# M105X.net
KiCad netlist of a schematic drawn in EAGLE
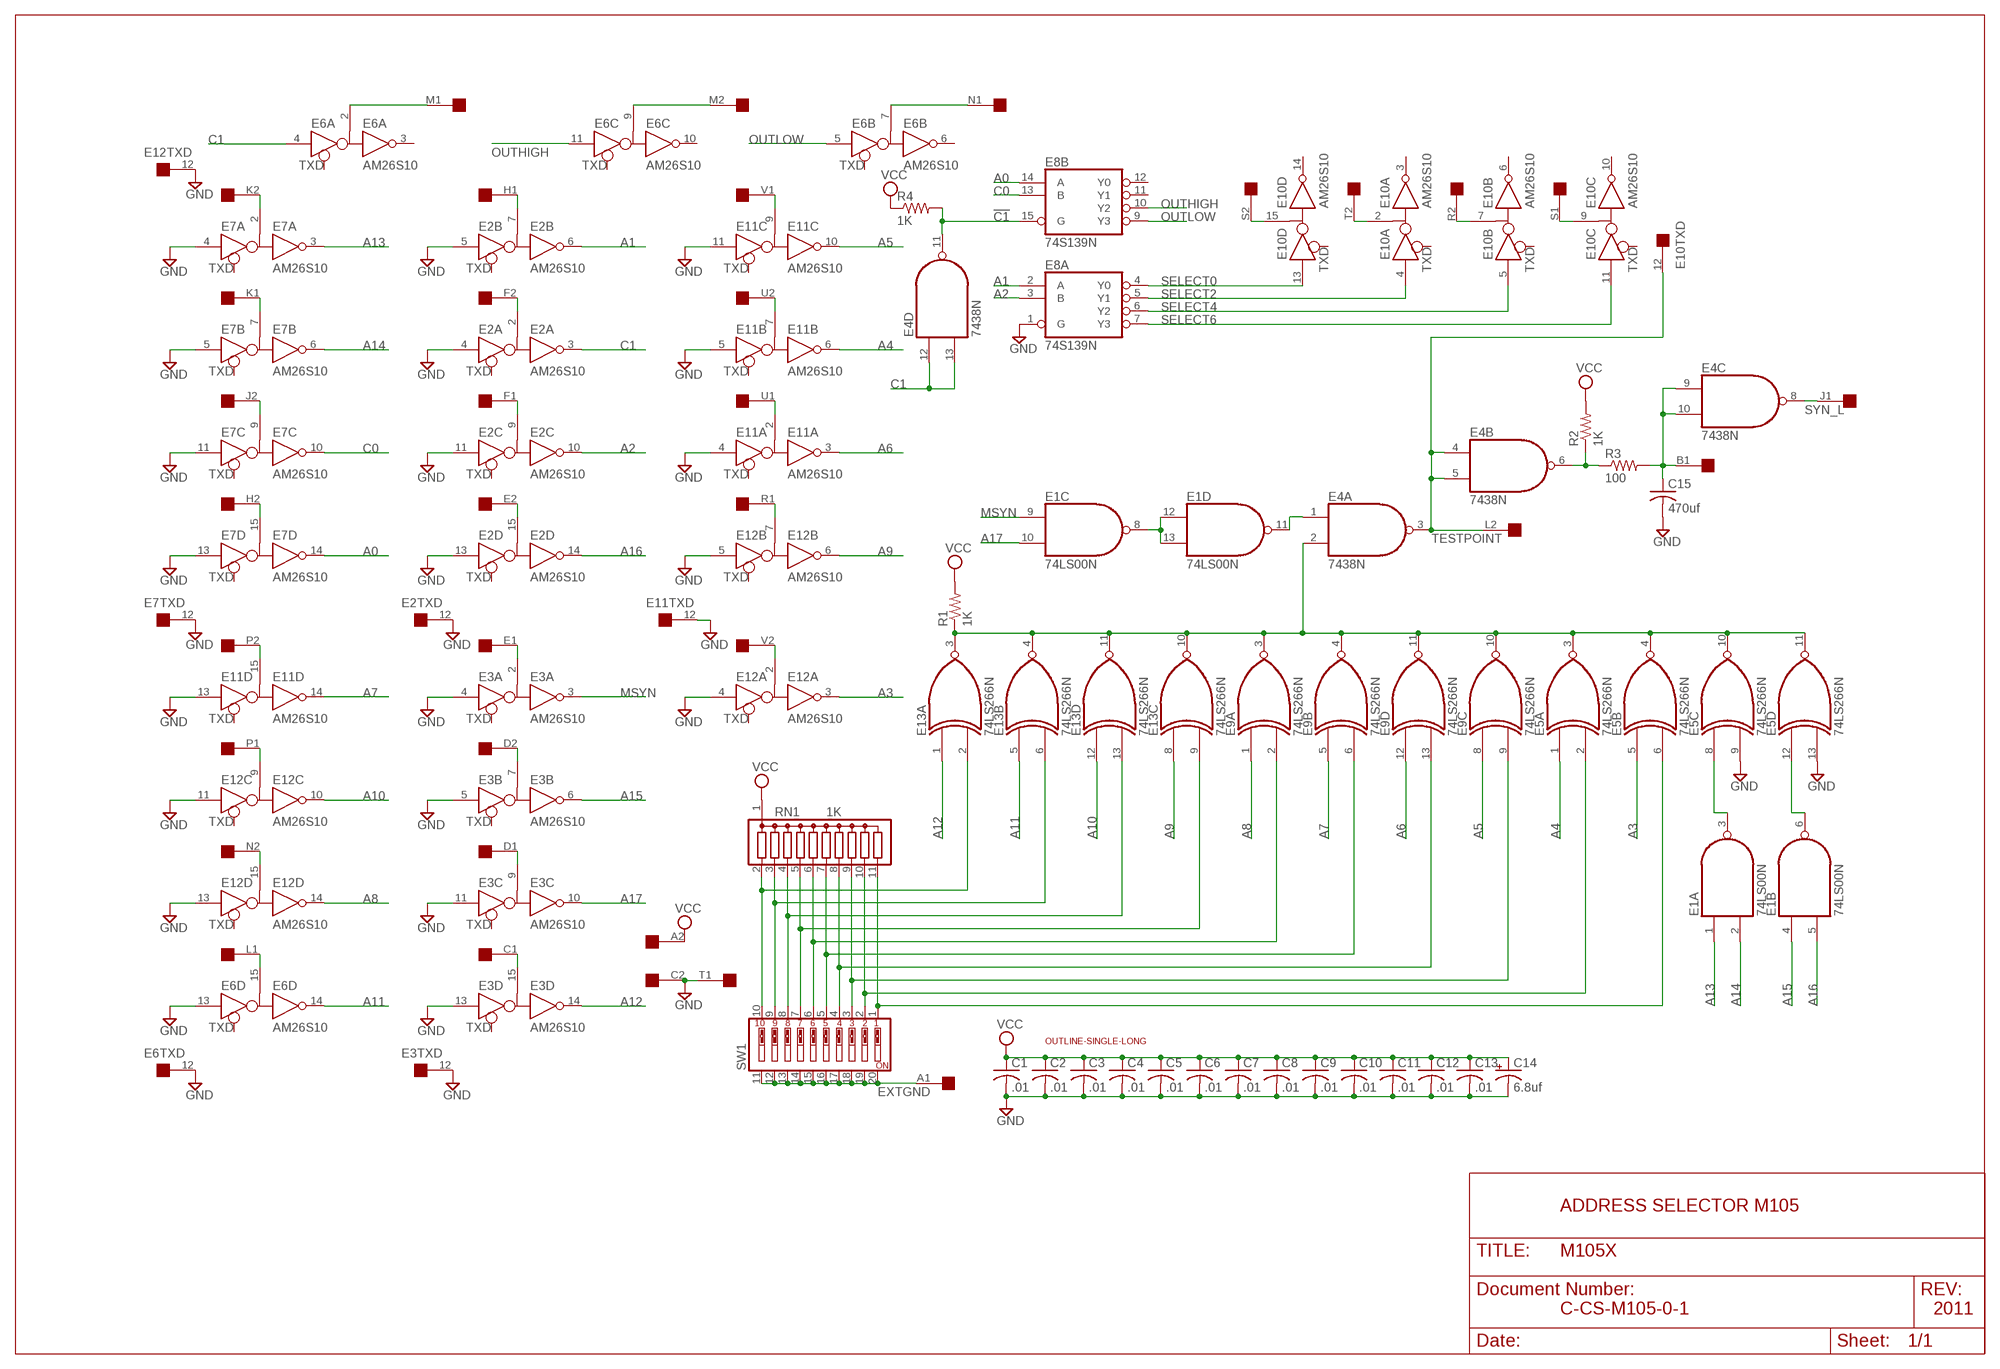
[diagram p0: schematic, sheet 1]

(export (version "E")
  (design (tool "Eeschema 10.0.6"))
  (components
    (comp (ref "C1")
      (value ".01")
      (footprint "eagle-import:C050-025X075")
      (libsource (lib "eagle-import") (part "C-US050-025X075"))
    )
    (comp (ref "C2")
      (value ".01")
      (footprint "eagle-import:C050-025X075")
      (libsource (lib "eagle-import") (part "C-US050-025X075"))
    )
    (comp (ref "C3")
      (value ".01")
      (footprint "eagle-import:C050-025X075")
      (libsource (lib "eagle-import") (part "C-US050-025X075"))
    )
    (comp (ref "C4")
      (value ".01")
      (footprint "eagle-import:C050-025X075")
      (libsource (lib "eagle-import") (part "C-US050-025X075"))
    )
    (comp (ref "C5")
      (value ".01")
      (footprint "eagle-import:C050-025X075")
      (libsource (lib "eagle-import") (part "C-US050-025X075"))
    )
    (comp (ref "C6")
      (value ".01")
      (footprint "eagle-import:C050-025X075")
      (libsource (lib "eagle-import") (part "C-US050-025X075"))
    )
    (comp (ref "C7")
      (value ".01")
      (footprint "eagle-import:C050-025X075")
      (libsource (lib "eagle-import") (part "C-US050-025X075"))
    )
    (comp (ref "C8")
      (value ".01")
      (footprint "eagle-import:C050-025X075")
      (libsource (lib "eagle-import") (part "C-US050-025X075"))
    )
    (comp (ref "C9")
      (value ".01")
      (footprint "eagle-import:C050-025X075")
      (libsource (lib "eagle-import") (part "C-US050-025X075"))
    )
    (comp (ref "C10")
      (value ".01")
      (footprint "eagle-import:C050-025X075")
      (libsource (lib "eagle-import") (part "C-US050-025X075"))
    )
    (comp (ref "C11")
      (value ".01")
      (footprint "eagle-import:C050-025X075")
      (libsource (lib "eagle-import") (part "C-US050-025X075"))
    )
    (comp (ref "C12")
      (value ".01")
      (footprint "eagle-import:C050-025X075")
      (libsource (lib "eagle-import") (part "C-US050-025X075"))
    )
    (comp (ref "C13")
      (value ".01")
      (footprint "eagle-import:C050-025X075")
      (libsource (lib "eagle-import") (part "C-US050-025X075"))
    )
    (comp (ref "C14")
      (value "6.8uf")
      (footprint "eagle-import:E15-5")
      (libsource (lib "eagle-import") (part "CPOL-USE15-5AXIAL"))
    )
    (comp (ref "C15")
      (value "470uf")
      (footprint "eagle-import:C050-025X075")
      (libsource (lib "eagle-import") (part "C-US050-025X075"))
    )
    (comp (ref "E1")
      (value "74LS00N")
      (footprint "eagle-import:DIL14")
      (libsource (lib "eagle-import") (part "7400NLS"))
    )
    (comp (ref "E2")
      (value "AM26S10")
      (footprint "eagle-import:DIL16")
      (libsource (lib "eagle-import") (part "AM26S10"))
    )
    (comp (ref "E3")
      (value "AM26S10")
      (footprint "eagle-import:DIL16")
      (libsource (lib "eagle-import") (part "AM26S10"))
    )
    (comp (ref "E4")
      (value "7438N")
      (footprint "eagle-import:DIL14")
      (libsource (lib "eagle-import") (part "7438N"))
    )
    (comp (ref "E5")
      (value "74LS266N")
      (footprint "eagle-import:DIL14")
      (libsource (lib "eagle-import") (part "74266NLS"))
    )
    (comp (ref "E6")
      (value "AM26S10")
      (footprint "eagle-import:DIL16")
      (libsource (lib "eagle-import") (part "AM26S10"))
    )
    (comp (ref "E7")
      (value "AM26S10")
      (footprint "eagle-import:DIL16")
      (libsource (lib "eagle-import") (part "AM26S10"))
    )
    (comp (ref "E8")
      (value "74S139N")
      (footprint "eagle-import:DIL16")
      (libsource (lib "eagle-import") (part "74139NS"))
    )
    (comp (ref "E9")
      (value "74LS266N")
      (footprint "eagle-import:DIL14")
      (libsource (lib "eagle-import") (part "74266NLS"))
    )
    (comp (ref "E10")
      (value "AM26S10")
      (footprint "eagle-import:DIL16")
      (libsource (lib "eagle-import") (part "AM26S10"))
    )
    (comp (ref "E11")
      (value "AM26S10")
      (footprint "eagle-import:DIL16")
      (libsource (lib "eagle-import") (part "AM26S10"))
    )
    (comp (ref "E12")
      (value "AM26S10")
      (footprint "eagle-import:DIL16")
      (libsource (lib "eagle-import") (part "AM26S10"))
    )
    (comp (ref "E13")
      (value "74LS266N")
      (footprint "eagle-import:DIL14")
      (libsource (lib "eagle-import") (part "74266NLS"))
    )
    (comp (ref "R1")
      (value "1K")
      (footprint "eagle-import:0207_10")
      (libsource (lib "eagle-import") (part "R-US_0207/10"))
    )
    (comp (ref "R2")
      (value "1K")
      (footprint "eagle-import:0207_10")
      (libsource (lib "eagle-import") (part "R-US_0207/10"))
    )
    (comp (ref "R3")
      (value "100")
      (footprint "eagle-import:0207_10")
      (libsource (lib "eagle-import") (part "R-US_0207/10"))
    )
    (comp (ref "R4")
      (value "1K")
      (footprint "eagle-import:0207_10")
      (libsource (lib "eagle-import") (part "R-US_0207/10"))
    )
    (comp (ref "RN1")
      (value "1K")
      (footprint "eagle-import:SIL11")
      (libsource (lib "eagle-import") (part "G10R"))
    )
    (comp (ref "SW1")
      (value "SW_DIP-10")
      (footprint "eagle-import:EDG-10")
      (libsource (lib "eagle-import") (part "SW_DIP-10"))
    )
    (comp (ref "U$1")
      (value "SINGLE")
      (footprint "eagle-import:EDGE-CON2")
      (libsource (lib "eagle-import") (part "SINGLE"))
    )
    (comp (ref "U$2")
      (value "OUTLINE-SINGLE-LONG")
      (footprint "eagle-import:SINGLE-LONG")
      (libsource (lib "eagle-import") (part "OUTLINE-SINGLE-LONG"))
    )
  )
  (nets
    (net (code "1") (name "/A0") (class "Default")
      (node (ref "E7") (pin "14") (pinfunction "R_14") (pintype "output"))
      (node (ref "E8") (pin "14") (pinfunction "A_14") (pintype "input"))
    )
    (net (code "2") (name "/A1") (class "Default")
      (node (ref "E2") (pin "6") (pinfunction "R_6") (pintype "output"))
      (node (ref "E8") (pin "2") (pinfunction "A_2") (pintype "input"))
    )
    (net (code "3") (name "/A2") (class "Default")
      (node (ref "E2") (pin "10") (pinfunction "R_10") (pintype "output"))
      (node (ref "E8") (pin "3") (pinfunction "B_3") (pintype "input"))
    )
    (net (code "4") (name "/A3") (class "Default")
      (node (ref "E12") (pin "3") (pinfunction "R_3") (pintype "output"))
      (node (ref "E5") (pin "5") (pinfunction "I0_5") (pintype "input"))
    )
    (net (code "5") (name "/A4") (class "Default")
      (node (ref "E11") (pin "6") (pinfunction "R_6") (pintype "output"))
      (node (ref "E5") (pin "1") (pinfunction "I0_1") (pintype "input"))
    )
    (net (code "6") (name "/A5") (class "Default")
      (node (ref "E11") (pin "10") (pinfunction "R_10") (pintype "output"))
      (node (ref "E9") (pin "8") (pinfunction "I0_8") (pintype "input"))
    )
    (net (code "7") (name "/A6") (class "Default")
      (node (ref "E11") (pin "3") (pinfunction "R_3") (pintype "output"))
      (node (ref "E9") (pin "12") (pinfunction "I0_12") (pintype "input"))
    )
    (net (code "8") (name "/A7") (class "Default")
      (node (ref "E11") (pin "14") (pinfunction "R_14") (pintype "output"))
      (node (ref "E9") (pin "5") (pinfunction "I0_5") (pintype "input"))
    )
    (net (code "9") (name "/A8") (class "Default")
      (node (ref "E12") (pin "14") (pinfunction "R_14") (pintype "output"))
      (node (ref "E9") (pin "1") (pinfunction "I0_1") (pintype "input"))
    )
    (net (code "10") (name "/A9") (class "Default")
      (node (ref "E12") (pin "6") (pinfunction "R_6") (pintype "output"))
      (node (ref "E13") (pin "8") (pinfunction "I0_8") (pintype "input"))
    )
    (net (code "11") (name "/A10") (class "Default")
      (node (ref "E12") (pin "10") (pinfunction "R_10") (pintype "output"))
      (node (ref "E13") (pin "12") (pinfunction "I0_12") (pintype "input"))
    )
    (net (code "12") (name "/A11") (class "Default")
      (node (ref "E13") (pin "5") (pinfunction "I0_5") (pintype "input"))
      (node (ref "E6") (pin "14") (pinfunction "R_14") (pintype "output"))
    )
    (net (code "13") (name "/A12") (class "Default")
      (node (ref "E13") (pin "1") (pinfunction "I0_1") (pintype "input"))
      (node (ref "E3") (pin "14") (pinfunction "R_14") (pintype "output"))
    )
    (net (code "14") (name "/A13") (class "Default")
      (node (ref "E1") (pin "1") (pinfunction "I0_1") (pintype "input"))
      (node (ref "E7") (pin "3") (pinfunction "R_3") (pintype "output"))
    )
    (net (code "15") (name "/A14") (class "Default")
      (node (ref "E1") (pin "2") (pinfunction "I1_2") (pintype "input"))
      (node (ref "E7") (pin "6") (pinfunction "R_6") (pintype "output"))
    )
    (net (code "16") (name "/A15") (class "Default")
      (node (ref "E1") (pin "4") (pinfunction "I0_4") (pintype "input"))
      (node (ref "E3") (pin "6") (pinfunction "R_6") (pintype "output"))
    )
    (net (code "17") (name "/A16") (class "Default")
      (node (ref "E1") (pin "5") (pinfunction "I1_5") (pintype "input"))
      (node (ref "E2") (pin "14") (pinfunction "R_14") (pintype "output"))
    )
    (net (code "18") (name "/A17") (class "Default")
      (node (ref "E1") (pin "10") (pinfunction "I1_10") (pintype "input"))
      (node (ref "E3") (pin "10") (pinfunction "R_10") (pintype "output"))
    )
    (net (code "19") (name "/C0") (class "Default")
      (node (ref "E7") (pin "10") (pinfunction "R_10") (pintype "output"))
      (node (ref "E8") (pin "13") (pinfunction "B_13") (pintype "input"))
    )
    (net (code "20") (name "/C1") (class "Default")
      (node (ref "E2") (pin "3") (pinfunction "R_3") (pintype "output"))
      (node (ref "E4") (pin "12") (pinfunction "I0_12") (pintype "input"))
      (node (ref "E4") (pin "13") (pinfunction "I1_13") (pintype "input"))
      (node (ref "E6") (pin "4") (pinfunction "D_4") (pintype "input"))
    )
    (net (code "21") (name "/EXTGND") (class "Default")
      (node (ref "SW1") (pin "11") (pinfunction "11_11") (pintype "passive"))
      (node (ref "SW1") (pin "12") (pinfunction "12_12") (pintype "passive"))
      (node (ref "SW1") (pin "13") (pinfunction "13_13") (pintype "passive"))
      (node (ref "SW1") (pin "14") (pinfunction "14_14") (pintype "passive"))
      (node (ref "SW1") (pin "15") (pinfunction "15_15") (pintype "passive"))
      (node (ref "SW1") (pin "16") (pinfunction "16_16") (pintype "passive"))
      (node (ref "SW1") (pin "17") (pinfunction "17_17") (pintype "passive"))
      (node (ref "SW1") (pin "18") (pinfunction "18_18") (pintype "passive"))
      (node (ref "SW1") (pin "19") (pinfunction "19_19") (pintype "passive"))
      (node (ref "SW1") (pin "20") (pinfunction "20_20") (pintype "passive"))
      (node (ref "U$1") (pin "A1") (pinfunction "1_A1") (pintype "bidirectional"))
    )
    (net (code "22") (name "/MSYN") (class "Default")
      (node (ref "E1") (pin "9") (pinfunction "I0_9") (pintype "input"))
      (node (ref "E3") (pin "3") (pinfunction "R_3") (pintype "output"))
    )
    (net (code "23") (name "/OUTHIGH") (class "Default")
      (node (ref "E6") (pin "11") (pinfunction "D_11") (pintype "input"))
      (node (ref "E8") (pin "10") (pinfunction "Y2_10") (pintype "output"))
    )
    (net (code "24") (name "/OUTLOW") (class "Default")
      (node (ref "E6") (pin "5") (pinfunction "D_5") (pintype "input"))
      (node (ref "E8") (pin "9") (pinfunction "Y3_9") (pintype "output"))
    )
    (net (code "25") (name "/SELECT0") (class "Default")
      (node (ref "E10") (pin "13") (pinfunction "D_13") (pintype "input"))
      (node (ref "E8") (pin "4") (pinfunction "Y0_4") (pintype "output"))
    )
    (net (code "26") (name "/SELECT2") (class "Default")
      (node (ref "E10") (pin "4") (pinfunction "D_4") (pintype "input"))
      (node (ref "E8") (pin "5") (pinfunction "Y1_5") (pintype "output"))
    )
    (net (code "27") (name "/SELECT4") (class "Default")
      (node (ref "E10") (pin "5") (pinfunction "D_5") (pintype "input"))
      (node (ref "E8") (pin "6") (pinfunction "Y2_6") (pintype "output"))
    )
    (net (code "28") (name "/SELECT6") (class "Default")
      (node (ref "E10") (pin "11") (pinfunction "D_11") (pintype "input"))
      (node (ref "E8") (pin "7") (pinfunction "Y3_7") (pintype "output"))
    )
    (net (code "29") (name "/SYN_L") (class "Default")
      (node (ref "E4") (pin "8") (pinfunction "O_8") (pintype "open_collector"))
      (node (ref "U$1") (pin "J1") (pinfunction "1_J1") (pintype "bidirectional"))
    )
    (net (code "30") (name "/TESTPOINT") (class "Default")
      (node (ref "E10") (pin "12") (pinfunction "TXD_12") (pintype "input"))
      (node (ref "E4") (pin "3") (pinfunction "O_3") (pintype "open_collector"))
      (node (ref "E4") (pin "4") (pinfunction "I0_4") (pintype "input"))
      (node (ref "E4") (pin "5") (pinfunction "I1_5") (pintype "input"))
      (node (ref "U$1") (pin "L2") (pinfunction "1_L2") (pintype "bidirectional"))
    )
    (net (code "31") (name "/~{C1}") (class "Default")
      (node (ref "E4") (pin "11") (pinfunction "O_11") (pintype "open_collector"))
      (node (ref "E8") (pin "15") (pinfunction "G_15") (pintype "input"))
      (node (ref "R4") (pin "2") (pinfunction "2_2") (pintype "passive"))
    )
    (net (code "32") (name "GND") (class "Default")
      (node (ref "C1") (pin "2") (pinfunction "2_2") (pintype "passive"))
      (node (ref "C10") (pin "2") (pinfunction "2_2") (pintype "passive"))
      (node (ref "C11") (pin "2") (pinfunction "2_2") (pintype "passive"))
      (node (ref "C12") (pin "2") (pinfunction "2_2") (pintype "passive"))
      (node (ref "C13") (pin "2") (pinfunction "2_2") (pintype "passive"))
      (node (ref "C14") (pin "-") (pinfunction "-_-") (pintype "passive"))
      (node (ref "C15") (pin "2") (pinfunction "2_2") (pintype "passive"))
      (node (ref "C2") (pin "2") (pinfunction "2_2") (pintype "passive"))
      (node (ref "C3") (pin "2") (pinfunction "2_2") (pintype "passive"))
      (node (ref "C4") (pin "2") (pinfunction "2_2") (pintype "passive"))
      (node (ref "C5") (pin "2") (pinfunction "2_2") (pintype "passive"))
      (node (ref "C6") (pin "2") (pinfunction "2_2") (pintype "passive"))
      (node (ref "C7") (pin "2") (pinfunction "2_2") (pintype "passive"))
      (node (ref "C8") (pin "2") (pinfunction "2_2") (pintype "passive"))
      (node (ref "C9") (pin "2") (pinfunction "2_2") (pintype "passive"))
      (node (ref "E11") (pin "11") (pinfunction "D_11") (pintype "input"))
      (node (ref "E11") (pin "12") (pinfunction "TXD_12") (pintype "input"))
      (node (ref "E11") (pin "13") (pinfunction "D_13") (pintype "input"))
      (node (ref "E11") (pin "4") (pinfunction "D_4") (pintype "input"))
      (node (ref "E11") (pin "5") (pinfunction "D_5") (pintype "input"))
      (node (ref "E12") (pin "11") (pinfunction "D_11") (pintype "input"))
      (node (ref "E12") (pin "12") (pinfunction "TXD_12") (pintype "input"))
      (node (ref "E12") (pin "13") (pinfunction "D_13") (pintype "input"))
      (node (ref "E12") (pin "4") (pinfunction "D_4") (pintype "input"))
      (node (ref "E12") (pin "5") (pinfunction "D_5") (pintype "input"))
      (node (ref "E2") (pin "11") (pinfunction "D_11") (pintype "input"))
      (node (ref "E2") (pin "12") (pinfunction "TXD_12") (pintype "input"))
      (node (ref "E2") (pin "13") (pinfunction "D_13") (pintype "input"))
      (node (ref "E2") (pin "4") (pinfunction "D_4") (pintype "input"))
      (node (ref "E2") (pin "5") (pinfunction "D_5") (pintype "input"))
      (node (ref "E3") (pin "11") (pinfunction "D_11") (pintype "input"))
      (node (ref "E3") (pin "12") (pinfunction "TXD_12") (pintype "input"))
      (node (ref "E3") (pin "13") (pinfunction "D_13") (pintype "input"))
      (node (ref "E3") (pin "4") (pinfunction "D_4") (pintype "input"))
      (node (ref "E3") (pin "5") (pinfunction "D_5") (pintype "input"))
      (node (ref "E5") (pin "13") (pinfunction "I1_13") (pintype "input"))
      (node (ref "E5") (pin "9") (pinfunction "I1_9") (pintype "input"))
      (node (ref "E6") (pin "12") (pinfunction "TXD_12") (pintype "input"))
      (node (ref "E6") (pin "13") (pinfunction "D_13") (pintype "input"))
      (node (ref "E7") (pin "11") (pinfunction "D_11") (pintype "input"))
      (node (ref "E7") (pin "12") (pinfunction "TXD_12") (pintype "input"))
      (node (ref "E7") (pin "13") (pinfunction "D_13") (pintype "input"))
      (node (ref "E7") (pin "4") (pinfunction "D_4") (pintype "input"))
      (node (ref "E7") (pin "5") (pinfunction "D_5") (pintype "input"))
      (node (ref "E8") (pin "1") (pinfunction "G_1") (pintype "input"))
      (node (ref "U$1") (pin "C2") (pinfunction "1_C2") (pintype "bidirectional"))
      (node (ref "U$1") (pin "T1") (pinfunction "1_T1") (pintype "bidirectional"))
    )
    (net (code "33") (name "Net-(E1A-O)") (class "Default")
      (node (ref "E1") (pin "3") (pinfunction "O_3") (pintype "output"))
      (node (ref "E5") (pin "8") (pinfunction "I0_8") (pintype "input"))
    )
    (net (code "34") (name "Net-(E1B-O)") (class "Default")
      (node (ref "E1") (pin "6") (pinfunction "O_6") (pintype "output"))
      (node (ref "E5") (pin "12") (pinfunction "I0_12") (pintype "input"))
    )
    (net (code "35") (name "Net-(E1C-O)") (class "Default")
      (node (ref "E1") (pin "12") (pinfunction "I0_12") (pintype "input"))
      (node (ref "E1") (pin "13") (pinfunction "I1_13") (pintype "input"))
      (node (ref "E1") (pin "8") (pinfunction "O_8") (pintype "output"))
    )
    (net (code "36") (name "Net-(E1D-O)") (class "Default")
      (node (ref "E1") (pin "11") (pinfunction "O_11") (pintype "output"))
      (node (ref "E4") (pin "1") (pinfunction "I0_1") (pintype "input"))
    )
    (net (code "37") (name "Net-(E2A-B)") (class "Default")
      (node (ref "E2") (pin "2") (pinfunction "B_2") (pintype "bidirectional"))
      (node (ref "U$1") (pin "F2") (pinfunction "1_F2") (pintype "bidirectional"))
    )
    (net (code "38") (name "Net-(E2B-B)") (class "Default")
      (node (ref "E2") (pin "7") (pinfunction "B_7") (pintype "bidirectional"))
      (node (ref "U$1") (pin "H1") (pinfunction "1_H1") (pintype "bidirectional"))
    )
    (net (code "39") (name "Net-(E2C-B)") (class "Default")
      (node (ref "E2") (pin "9") (pinfunction "B_9") (pintype "bidirectional"))
      (node (ref "U$1") (pin "F1") (pinfunction "1_F1") (pintype "bidirectional"))
    )
    (net (code "40") (name "Net-(E2D-B)") (class "Default")
      (node (ref "E2") (pin "15") (pinfunction "B_15") (pintype "bidirectional"))
      (node (ref "U$1") (pin "E2") (pinfunction "1_E2") (pintype "bidirectional"))
    )
    (net (code "41") (name "Net-(E3A-B)") (class "Default")
      (node (ref "E3") (pin "2") (pinfunction "B_2") (pintype "bidirectional"))
      (node (ref "U$1") (pin "E1") (pinfunction "1_E1") (pintype "bidirectional"))
    )
    (net (code "42") (name "Net-(E3B-B)") (class "Default")
      (node (ref "E3") (pin "7") (pinfunction "B_7") (pintype "bidirectional"))
      (node (ref "U$1") (pin "D2") (pinfunction "1_D2") (pintype "bidirectional"))
    )
    (net (code "43") (name "Net-(E3C-B)") (class "Default")
      (node (ref "E3") (pin "9") (pinfunction "B_9") (pintype "bidirectional"))
      (node (ref "U$1") (pin "D1") (pinfunction "1_D1") (pintype "bidirectional"))
    )
    (net (code "44") (name "Net-(E3D-B)") (class "Default")
      (node (ref "E3") (pin "15") (pinfunction "B_15") (pintype "bidirectional"))
      (node (ref "U$1") (pin "C1") (pinfunction "1_C1") (pintype "bidirectional"))
    )
    (net (code "45") (name "Net-(E4B-O)") (class "Default")
      (node (ref "E4") (pin "6") (pinfunction "O_6") (pintype "open_collector"))
      (node (ref "R2") (pin "1") (pinfunction "1_1") (pintype "passive"))
      (node (ref "R3") (pin "1") (pinfunction "1_1") (pintype "passive"))
    )
    (net (code "46") (name "Net-(E4C-I0)") (class "Default")
      (node (ref "C15") (pin "1") (pinfunction "1_1") (pintype "passive"))
      (node (ref "E4") (pin "10") (pinfunction "I1_10") (pintype "input"))
      (node (ref "E4") (pin "9") (pinfunction "I0_9") (pintype "input"))
      (node (ref "R3") (pin "2") (pinfunction "2_2") (pintype "passive"))
      (node (ref "U$1") (pin "B1") (pinfunction "1_B1") (pintype "bidirectional"))
    )
    (net (code "47") (name "Net-(E5A-I1)") (class "Default")
      (node (ref "E5") (pin "2") (pinfunction "I1_2") (pintype "input"))
      (node (ref "RN1") (pin "10") (pinfunction "10_10") (pintype "passive"))
      (node (ref "SW1") (pin "2") (pinfunction "2_2") (pintype "passive"))
    )
    (net (code "48") (name "Net-(E5B-I1)") (class "Default")
      (node (ref "E5") (pin "6") (pinfunction "I1_6") (pintype "input"))
      (node (ref "RN1") (pin "11") (pinfunction "11_11") (pintype "passive"))
      (node (ref "SW1") (pin "1") (pinfunction "1_1") (pintype "passive"))
    )
    (net (code "49") (name "Net-(E6A-B)") (class "Default")
      (node (ref "E6") (pin "2") (pinfunction "B_2") (pintype "bidirectional"))
      (node (ref "U$1") (pin "M1") (pinfunction "1_M1") (pintype "bidirectional"))
    )
    (net (code "50") (name "Net-(E6B-B)") (class "Default")
      (node (ref "E6") (pin "7") (pinfunction "B_7") (pintype "bidirectional"))
      (node (ref "U$1") (pin "N1") (pinfunction "1_N1") (pintype "bidirectional"))
    )
    (net (code "51") (name "Net-(E6C-B)") (class "Default")
      (node (ref "E6") (pin "9") (pinfunction "B_9") (pintype "bidirectional"))
      (node (ref "U$1") (pin "M2") (pinfunction "1_M2") (pintype "bidirectional"))
    )
    (net (code "52") (name "Net-(E6D-B)") (class "Default")
      (node (ref "E6") (pin "15") (pinfunction "B_15") (pintype "bidirectional"))
      (node (ref "U$1") (pin "L1") (pinfunction "1_L1") (pintype "bidirectional"))
    )
    (net (code "53") (name "Net-(E7A-B)") (class "Default")
      (node (ref "E7") (pin "2") (pinfunction "B_2") (pintype "bidirectional"))
      (node (ref "U$1") (pin "K2") (pinfunction "1_K2") (pintype "bidirectional"))
    )
    (net (code "54") (name "Net-(E7B-B)") (class "Default")
      (node (ref "E7") (pin "7") (pinfunction "B_7") (pintype "bidirectional"))
      (node (ref "U$1") (pin "K1") (pinfunction "1_K1") (pintype "bidirectional"))
    )
    (net (code "55") (name "Net-(E7C-B)") (class "Default")
      (node (ref "E7") (pin "9") (pinfunction "B_9") (pintype "bidirectional"))
      (node (ref "U$1") (pin "J2") (pinfunction "1_J2") (pintype "bidirectional"))
    )
    (net (code "56") (name "Net-(E7D-B)") (class "Default")
      (node (ref "E7") (pin "15") (pinfunction "B_15") (pintype "bidirectional"))
      (node (ref "U$1") (pin "H2") (pinfunction "1_H2") (pintype "bidirectional"))
    )
    (net (code "57") (name "Net-(E9A-I1)") (class "Default")
      (node (ref "E9") (pin "2") (pinfunction "I1_2") (pintype "input"))
      (node (ref "RN1") (pin "6") (pinfunction "6_6") (pintype "passive"))
      (node (ref "SW1") (pin "6") (pinfunction "6_6") (pintype "passive"))
    )
    (net (code "58") (name "Net-(E9B-I1)") (class "Default")
      (node (ref "E9") (pin "6") (pinfunction "I1_6") (pintype "input"))
      (node (ref "RN1") (pin "7") (pinfunction "7_7") (pintype "passive"))
      (node (ref "SW1") (pin "5") (pinfunction "5_5") (pintype "passive"))
    )
    (net (code "59") (name "Net-(E9C-I1)") (class "Default")
      (node (ref "E9") (pin "9") (pinfunction "I1_9") (pintype "input"))
      (node (ref "RN1") (pin "9") (pinfunction "9_9") (pintype "passive"))
      (node (ref "SW1") (pin "3") (pinfunction "3_3") (pintype "passive"))
    )
    (net (code "60") (name "Net-(E9D-I1)") (class "Default")
      (node (ref "E9") (pin "13") (pinfunction "I1_13") (pintype "input"))
      (node (ref "RN1") (pin "8") (pinfunction "8_8") (pintype "passive"))
      (node (ref "SW1") (pin "4") (pinfunction "4_4") (pintype "passive"))
    )
    (net (code "61") (name "Net-(E10A-B)") (class "Default")
      (node (ref "E10") (pin "2") (pinfunction "B_2") (pintype "bidirectional"))
      (node (ref "U$1") (pin "T2") (pinfunction "1_T2") (pintype "bidirectional"))
    )
    (net (code "62") (name "Net-(E10B-B)") (class "Default")
      (node (ref "E10") (pin "7") (pinfunction "B_7") (pintype "bidirectional"))
      (node (ref "U$1") (pin "R2") (pinfunction "1_R2") (pintype "bidirectional"))
    )
    (net (code "63") (name "Net-(E10C-B)") (class "Default")
      (node (ref "E10") (pin "9") (pinfunction "B_9") (pintype "bidirectional"))
      (node (ref "U$1") (pin "S1") (pinfunction "1_S1") (pintype "bidirectional"))
    )
    (net (code "64") (name "Net-(E10D-B)") (class "Default")
      (node (ref "E10") (pin "15") (pinfunction "B_15") (pintype "bidirectional"))
      (node (ref "U$1") (pin "S2") (pinfunction "1_S2") (pintype "bidirectional"))
    )
    (net (code "65") (name "Net-(E11A-B)") (class "Default")
      (node (ref "E11") (pin "2") (pinfunction "B_2") (pintype "bidirectional"))
      (node (ref "U$1") (pin "U1") (pinfunction "1_U1") (pintype "bidirectional"))
    )
    (net (code "66") (name "Net-(E11B-B)") (class "Default")
      (node (ref "E11") (pin "7") (pinfunction "B_7") (pintype "bidirectional"))
      (node (ref "U$1") (pin "U2") (pinfunction "1_U2") (pintype "bidirectional"))
    )
    (net (code "67") (name "Net-(E11C-B)") (class "Default")
      (node (ref "E11") (pin "9") (pinfunction "B_9") (pintype "bidirectional"))
      (node (ref "U$1") (pin "V1") (pinfunction "1_V1") (pintype "bidirectional"))
    )
    (net (code "68") (name "Net-(E11D-B)") (class "Default")
      (node (ref "E11") (pin "15") (pinfunction "B_15") (pintype "bidirectional"))
      (node (ref "U$1") (pin "P2") (pinfunction "1_P2") (pintype "bidirectional"))
    )
    (net (code "69") (name "Net-(E12A-B)") (class "Default")
      (node (ref "E12") (pin "2") (pinfunction "B_2") (pintype "bidirectional"))
      (node (ref "U$1") (pin "V2") (pinfunction "1_V2") (pintype "bidirectional"))
    )
    (net (code "70") (name "Net-(E12B-B)") (class "Default")
      (node (ref "E12") (pin "7") (pinfunction "B_7") (pintype "bidirectional"))
      (node (ref "U$1") (pin "R1") (pinfunction "1_R1") (pintype "bidirectional"))
    )
    (net (code "71") (name "Net-(E12C-B)") (class "Default")
      (node (ref "E12") (pin "9") (pinfunction "B_9") (pintype "bidirectional"))
      (node (ref "U$1") (pin "P1") (pinfunction "1_P1") (pintype "bidirectional"))
    )
    (net (code "72") (name "Net-(E12D-B)") (class "Default")
      (node (ref "E12") (pin "15") (pinfunction "B_15") (pintype "bidirectional"))
      (node (ref "U$1") (pin "N2") (pinfunction "1_N2") (pintype "bidirectional"))
    )
    (net (code "73") (name "Net-(E13A-I1)") (class "Default")
      (node (ref "E13") (pin "2") (pinfunction "I1_2") (pintype "input"))
      (node (ref "RN1") (pin "2") (pinfunction "2_2") (pintype "passive"))
      (node (ref "SW1") (pin "10") (pinfunction "10_10") (pintype "passive"))
    )
    (net (code "74") (name "Net-(E13A-O)") (class "Default")
      (node (ref "E13") (pin "10") (pinfunction "O_10") (pintype "open_collector"))
      (node (ref "E13") (pin "11") (pinfunction "O_11") (pintype "open_collector"))
      (node (ref "E13") (pin "3") (pinfunction "O_3") (pintype "open_collector"))
      (node (ref "E13") (pin "4") (pinfunction "O_4") (pintype "open_collector"))
      (node (ref "E4") (pin "2") (pinfunction "I1_2") (pintype "input"))
      (node (ref "E5") (pin "10") (pinfunction "O_10") (pintype "open_collector"))
      (node (ref "E5") (pin "11") (pinfunction "O_11") (pintype "open_collector"))
      (node (ref "E5") (pin "3") (pinfunction "O_3") (pintype "open_collector"))
      (node (ref "E5") (pin "4") (pinfunction "O_4") (pintype "open_collector"))
      (node (ref "E9") (pin "10") (pinfunction "O_10") (pintype "open_collector"))
      (node (ref "E9") (pin "11") (pinfunction "O_11") (pintype "open_collector"))
      (node (ref "E9") (pin "3") (pinfunction "O_3") (pintype "open_collector"))
      (node (ref "E9") (pin "4") (pinfunction "O_4") (pintype "open_collector"))
      (node (ref "R1") (pin "1") (pinfunction "1_1") (pintype "passive"))
    )
    (net (code "75") (name "Net-(E13B-I1)") (class "Default")
      (node (ref "E13") (pin "6") (pinfunction "I1_6") (pintype "input"))
      (node (ref "RN1") (pin "3") (pinfunction "3_3") (pintype "passive"))
      (node (ref "SW1") (pin "9") (pinfunction "9_9") (pintype "passive"))
    )
    (net (code "76") (name "Net-(E13C-I1)") (class "Default")
      (node (ref "E13") (pin "9") (pinfunction "I1_9") (pintype "input"))
      (node (ref "RN1") (pin "5") (pinfunction "5_5") (pintype "passive"))
      (node (ref "SW1") (pin "7") (pinfunction "7_7") (pintype "passive"))
    )
    (net (code "77") (name "Net-(E13D-I1)") (class "Default")
      (node (ref "E13") (pin "13") (pinfunction "I1_13") (pintype "input"))
      (node (ref "RN1") (pin "4") (pinfunction "4_4") (pintype "passive"))
      (node (ref "SW1") (pin "8") (pinfunction "8_8") (pintype "passive"))
    )
    (net (code "78") (name "VCC") (class "Default")
      (node (ref "C1") (pin "1") (pinfunction "1_1") (pintype "passive"))
      (node (ref "C10") (pin "1") (pinfunction "1_1") (pintype "passive"))
      (node (ref "C11") (pin "1") (pinfunction "1_1") (pintype "passive"))
      (node (ref "C12") (pin "1") (pinfunction "1_1") (pintype "passive"))
      (node (ref "C13") (pin "1") (pinfunction "1_1") (pintype "passive"))
      (node (ref "C14") (pin "+") (pinfunction "+_+") (pintype "passive"))
      (node (ref "C2") (pin "1") (pinfunction "1_1") (pintype "passive"))
      (node (ref "C3") (pin "1") (pinfunction "1_1") (pintype "passive"))
      (node (ref "C4") (pin "1") (pinfunction "1_1") (pintype "passive"))
      (node (ref "C5") (pin "1") (pinfunction "1_1") (pintype "passive"))
      (node (ref "C6") (pin "1") (pinfunction "1_1") (pintype "passive"))
      (node (ref "C7") (pin "1") (pinfunction "1_1") (pintype "passive"))
      (node (ref "C8") (pin "1") (pinfunction "1_1") (pintype "passive"))
      (node (ref "C9") (pin "1") (pinfunction "1_1") (pintype "passive"))
      (node (ref "R1") (pin "2") (pinfunction "2_2") (pintype "passive"))
      (node (ref "R2") (pin "2") (pinfunction "2_2") (pintype "passive"))
      (node (ref "R4") (pin "1") (pinfunction "1_1") (pintype "passive"))
      (node (ref "RN1") (pin "1") (pinfunction "1_1") (pintype "passive"))
      (node (ref "U$1") (pin "A2") (pinfunction "1_A2") (pintype "bidirectional"))
    )
    (net (code "79") (name "unconnected-(E6A-R-Pad3)") (class "Default")
      (node (ref "E6") (pin "3") (pinfunction "R_3") (pintype "output"))
    )
    (net (code "80") (name "unconnected-(E6B-R-Pad6)") (class "Default")
      (node (ref "E6") (pin "6") (pinfunction "R_6") (pintype "output"))
    )
    (net (code "81") (name "unconnected-(E6C-R-Pad10)") (class "Default")
      (node (ref "E6") (pin "10") (pinfunction "R_10") (pintype "output"))
    )
    (net (code "82") (name "unconnected-(E8B-Y0-Pad12)") (class "Default")
      (node (ref "E8") (pin "12") (pinfunction "Y0_12") (pintype "output"))
    )
    (net (code "83") (name "unconnected-(E8B-Y1-Pad11)") (class "Default")
      (node (ref "E8") (pin "11") (pinfunction "Y1_11") (pintype "output"))
    )
    (net (code "84") (name "unconnected-(E10A-R-Pad3)") (class "Default")
      (node (ref "E10") (pin "3") (pinfunction "R_3") (pintype "output"))
    )
    (net (code "85") (name "unconnected-(E10B-R-Pad6)") (class "Default")
      (node (ref "E10") (pin "6") (pinfunction "R_6") (pintype "output"))
    )
    (net (code "86") (name "unconnected-(E10C-R-Pad10)") (class "Default")
      (node (ref "E10") (pin "10") (pinfunction "R_10") (pintype "output"))
    )
    (net (code "87") (name "unconnected-(E10D-R-Pad14)") (class "Default")
      (node (ref "E10") (pin "14") (pinfunction "R_14") (pintype "output"))
    )
  )
)
